# meca_2014_VaccumSystemExtension.net
KiCad netlist of a schematic drawn in EAGLE
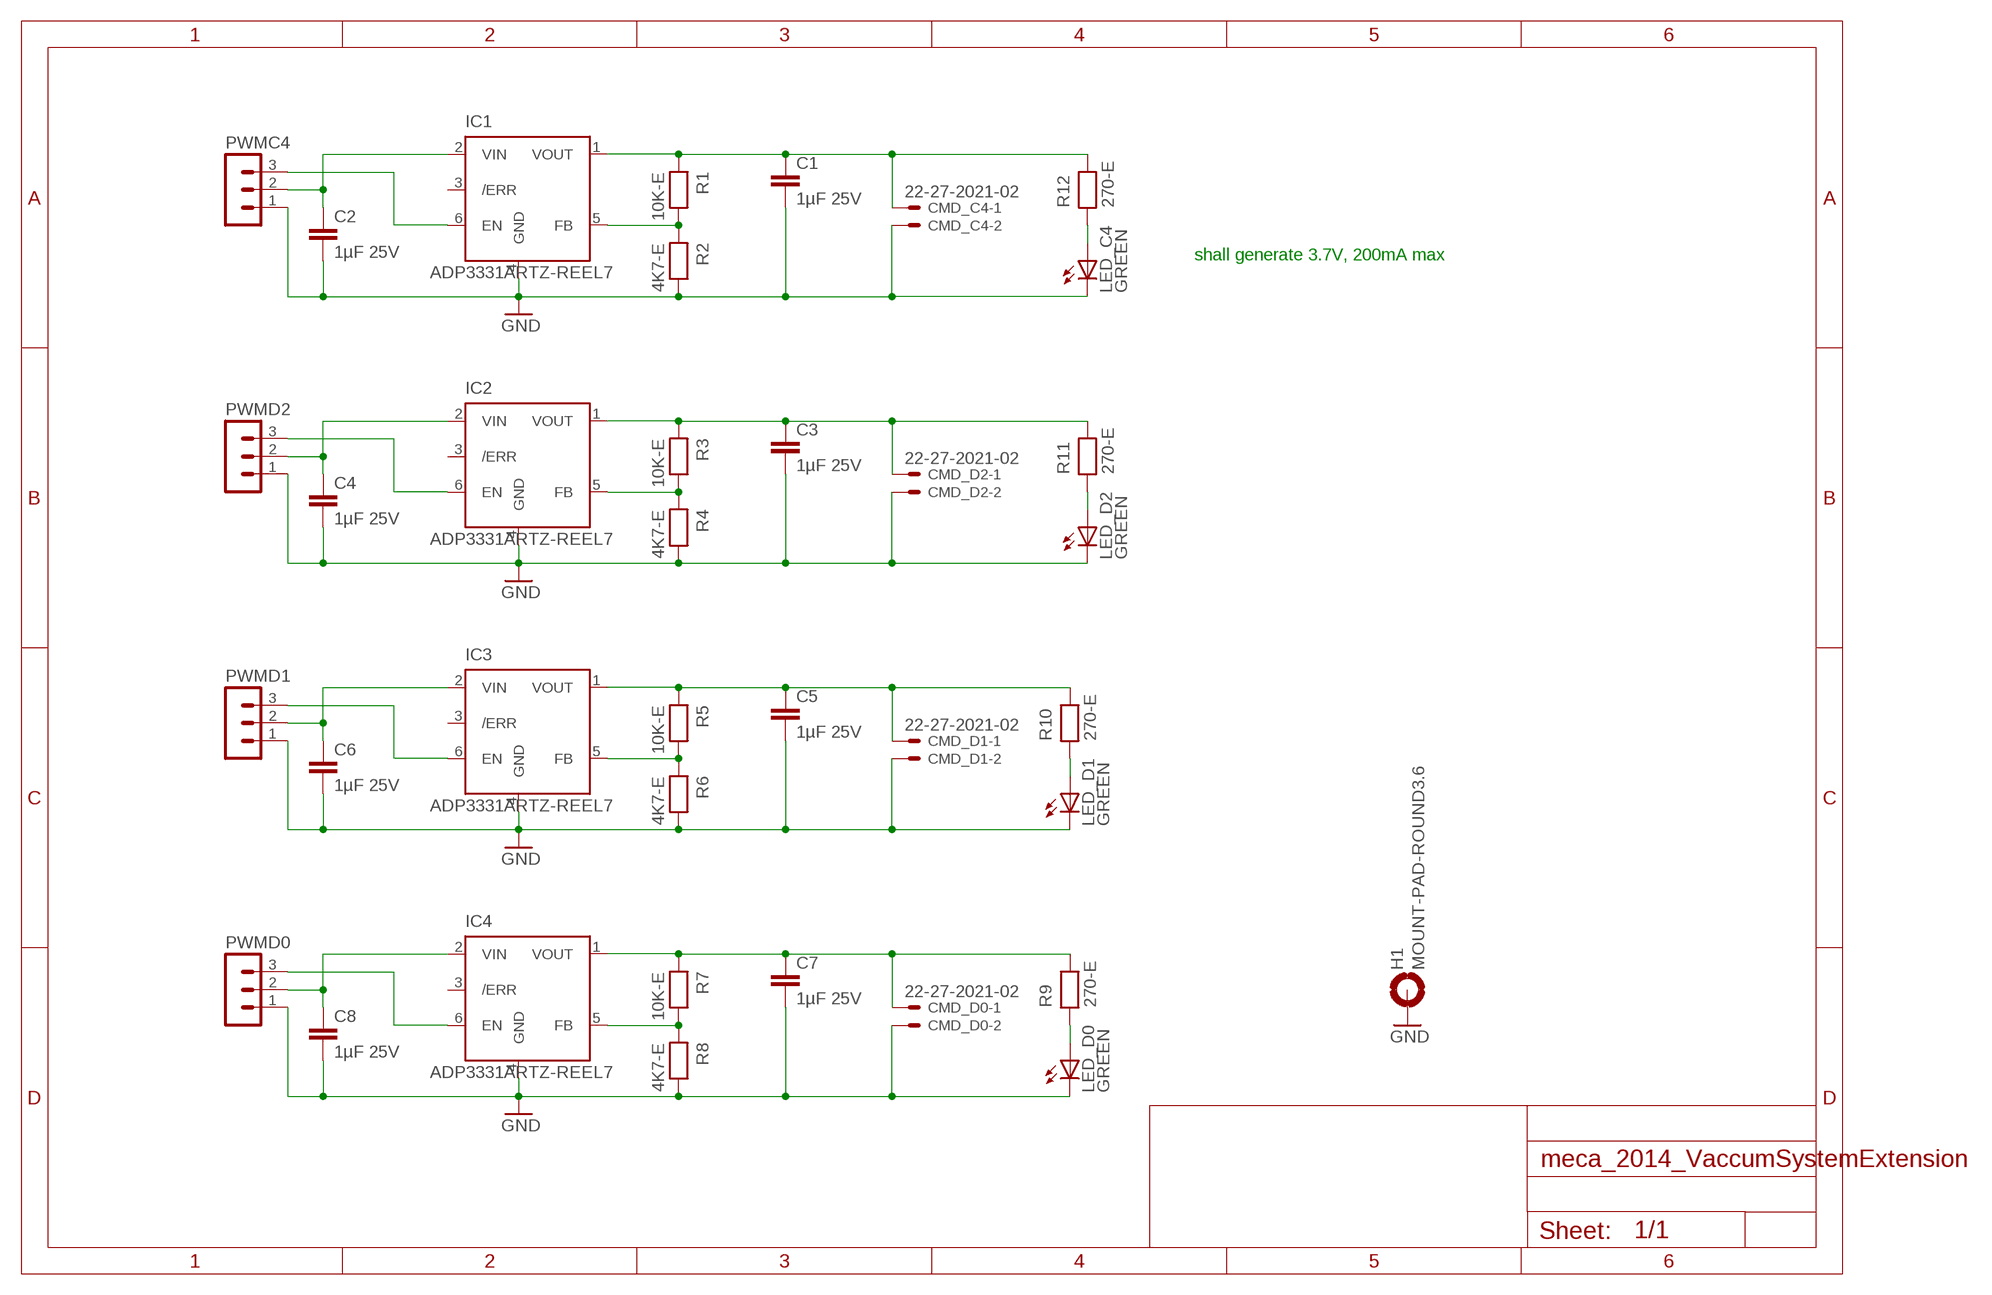
[diagram p0: schematic, sheet 1]

(export (version "E")
  (design (tool "Eeschema 10.0.6"))
  (components
    (comp (ref "C1")
      (value "1µF 25V")
      (footprint "eagle-import:C1206")
      (libsource (lib "eagle-import") (part "1UFD_25V"))
    )
    (comp (ref "C2")
      (value "1µF 25V")
      (footprint "eagle-import:C1206")
      (libsource (lib "eagle-import") (part "1UFD_25V"))
    )
    (comp (ref "C3")
      (value "1µF 25V")
      (footprint "eagle-import:C1206")
      (libsource (lib "eagle-import") (part "1UFD_25V"))
    )
    (comp (ref "C4")
      (value "1µF 25V")
      (footprint "eagle-import:C1206")
      (libsource (lib "eagle-import") (part "1UFD_25V"))
    )
    (comp (ref "C5")
      (value "1µF 25V")
      (footprint "eagle-import:C1206")
      (libsource (lib "eagle-import") (part "1UFD_25V"))
    )
    (comp (ref "C6")
      (value "1µF 25V")
      (footprint "eagle-import:C1206")
      (libsource (lib "eagle-import") (part "1UFD_25V"))
    )
    (comp (ref "C7")
      (value "1µF 25V")
      (footprint "eagle-import:C1206")
      (libsource (lib "eagle-import") (part "1UFD_25V"))
    )
    (comp (ref "C8")
      (value "1µF 25V")
      (footprint "eagle-import:C1206")
      (libsource (lib "eagle-import") (part "1UFD_25V"))
    )
    (comp (ref "CMD_C4")
      (value "22-27-2021-02")
      (footprint "eagle-import:6410-02")
      (libsource (lib "eagle-import") (part "22-?-0227-2021"))
    )
    (comp (ref "CMD_D0")
      (value "22-27-2021-02")
      (footprint "eagle-import:6410-02")
      (libsource (lib "eagle-import") (part "22-?-0227-2021"))
    )
    (comp (ref "CMD_D1")
      (value "22-27-2021-02")
      (footprint "eagle-import:6410-02")
      (libsource (lib "eagle-import") (part "22-?-0227-2021"))
    )
    (comp (ref "CMD_D2")
      (value "22-27-2021-02")
      (footprint "eagle-import:6410-02")
      (libsource (lib "eagle-import") (part "22-?-0227-2021"))
    )
    (comp (ref "H1")
      (value "MOUNT-PAD-ROUND3.6")
      (footprint "eagle-import:3,6-PAD")
      (libsource (lib "eagle-import") (part "MOUNT-PAD-ROUND3.6"))
    )
    (comp (ref "IC1")
      (value "ADP3331ARTZ-REEL7")
      (footprint "eagle-import:SOT23-6")
      (libsource (lib "eagle-import") (part "ADP3331ARTZ-REEL7"))
    )
    (comp (ref "IC2")
      (value "ADP3331ARTZ-REEL7")
      (footprint "eagle-import:SOT23-6")
      (libsource (lib "eagle-import") (part "ADP3331ARTZ-REEL7"))
    )
    (comp (ref "IC3")
      (value "ADP3331ARTZ-REEL7")
      (footprint "eagle-import:SOT23-6")
      (libsource (lib "eagle-import") (part "ADP3331ARTZ-REEL7"))
    )
    (comp (ref "IC4")
      (value "ADP3331ARTZ-REEL7")
      (footprint "eagle-import:SOT23-6")
      (libsource (lib "eagle-import") (part "ADP3331ARTZ-REEL7"))
    )
    (comp (ref "LED_C4")
      (value "GREEN")
      (footprint "eagle-import:CHIP-LED0805")
      (libsource (lib "eagle-import") (part "LED_G"))
    )
    (comp (ref "LED_D0")
      (value "GREEN")
      (footprint "eagle-import:CHIP-LED0805")
      (libsource (lib "eagle-import") (part "LED_G"))
    )
    (comp (ref "LED_D1")
      (value "GREEN")
      (footprint "eagle-import:CHIP-LED0805")
      (libsource (lib "eagle-import") (part "LED_G"))
    )
    (comp (ref "LED_D2")
      (value "GREEN")
      (footprint "eagle-import:CHIP-LED0805")
      (libsource (lib "eagle-import") (part "LED_G"))
    )
    (comp (ref "PWMC4")
      (value "MA03-1")
      (footprint "eagle-import:MA03-1")
      (libsource (lib "eagle-import") (part "MA03-1"))
    )
    (comp (ref "PWMD0")
      (value "MA03-1")
      (footprint "eagle-import:MA03-1")
      (libsource (lib "eagle-import") (part "MA03-1"))
    )
    (comp (ref "PWMD1")
      (value "MA03-1")
      (footprint "eagle-import:MA03-1")
      (libsource (lib "eagle-import") (part "MA03-1"))
    )
    (comp (ref "PWMD2")
      (value "MA03-1")
      (footprint "eagle-import:MA03-1")
      (libsource (lib "eagle-import") (part "MA03-1"))
    )
    (comp (ref "R1")
      (value "10K-E")
      (footprint "eagle-import:R0805")
      (libsource (lib "eagle-import") (part "10K-E"))
    )
    (comp (ref "R2")
      (value "4K7-E")
      (footprint "eagle-import:R0805")
      (libsource (lib "eagle-import") (part "4K7-E"))
    )
    (comp (ref "R3")
      (value "10K-E")
      (footprint "eagle-import:R0805")
      (libsource (lib "eagle-import") (part "10K-E"))
    )
    (comp (ref "R4")
      (value "4K7-E")
      (footprint "eagle-import:R0805")
      (libsource (lib "eagle-import") (part "4K7-E"))
    )
    (comp (ref "R5")
      (value "10K-E")
      (footprint "eagle-import:R0805")
      (libsource (lib "eagle-import") (part "10K-E"))
    )
    (comp (ref "R6")
      (value "4K7-E")
      (footprint "eagle-import:R0805")
      (libsource (lib "eagle-import") (part "4K7-E"))
    )
    (comp (ref "R7")
      (value "10K-E")
      (footprint "eagle-import:R0805")
      (libsource (lib "eagle-import") (part "10K-E"))
    )
    (comp (ref "R8")
      (value "4K7-E")
      (footprint "eagle-import:R0805")
      (libsource (lib "eagle-import") (part "4K7-E"))
    )
    (comp (ref "R9")
      (value "270-E")
      (footprint "eagle-import:R0805")
      (libsource (lib "eagle-import") (part "270-E"))
    )
    (comp (ref "R10")
      (value "270-E")
      (footprint "eagle-import:R0805")
      (libsource (lib "eagle-import") (part "270-E"))
    )
    (comp (ref "R11")
      (value "270-E")
      (footprint "eagle-import:R0805")
      (libsource (lib "eagle-import") (part "270-E"))
    )
    (comp (ref "R12")
      (value "270-E")
      (footprint "eagle-import:R0805")
      (libsource (lib "eagle-import") (part "270-E"))
    )
  )
  (nets
    (net (code "1") (name "GND") (class "Default")
      (node (ref "C1") (pin "2") (pinfunction "2_2") (pintype "passive"))
      (node (ref "C2") (pin "2") (pinfunction "2_2") (pintype "passive"))
      (node (ref "C3") (pin "2") (pinfunction "2_2") (pintype "passive"))
      (node (ref "C4") (pin "2") (pinfunction "2_2") (pintype "passive"))
      (node (ref "C5") (pin "2") (pinfunction "2_2") (pintype "passive"))
      (node (ref "C6") (pin "2") (pinfunction "2_2") (pintype "passive"))
      (node (ref "C7") (pin "2") (pinfunction "2_2") (pintype "passive"))
      (node (ref "C8") (pin "2") (pinfunction "2_2") (pintype "passive"))
      (node (ref "CMD_C4") (pin "2") (pinfunction "S_2") (pintype "passive"))
      (node (ref "CMD_D0") (pin "2") (pinfunction "S_2") (pintype "passive"))
      (node (ref "CMD_D1") (pin "2") (pinfunction "S_2") (pintype "passive"))
      (node (ref "CMD_D2") (pin "2") (pinfunction "S_2") (pintype "passive"))
      (node (ref "H1") (pin "B3,6") (pinfunction "MOUNT_B3,6") (pintype "passive"))
      (node (ref "IC1") (pin "4") (pinfunction "GND_4") (pintype "bidirectional"))
      (node (ref "IC2") (pin "4") (pinfunction "GND_4") (pintype "bidirectional"))
      (node (ref "IC3") (pin "4") (pinfunction "GND_4") (pintype "bidirectional"))
      (node (ref "IC4") (pin "4") (pinfunction "GND_4") (pintype "bidirectional"))
      (node (ref "LED_C4") (pin "C") (pinfunction "C_C") (pintype "passive"))
      (node (ref "LED_D0") (pin "C") (pinfunction "C_C") (pintype "passive"))
      (node (ref "LED_D1") (pin "C") (pinfunction "C_C") (pintype "passive"))
      (node (ref "LED_D2") (pin "C") (pinfunction "C_C") (pintype "passive"))
      (node (ref "PWMC4") (pin "1") (pinfunction "1_1") (pintype "passive"))
      (node (ref "PWMD0") (pin "1") (pinfunction "1_1") (pintype "passive"))
      (node (ref "PWMD1") (pin "1") (pinfunction "1_1") (pintype "passive"))
      (node (ref "PWMD2") (pin "1") (pinfunction "1_1") (pintype "passive"))
      (node (ref "R2") (pin "2") (pinfunction "2_2") (pintype "bidirectional"))
      (node (ref "R4") (pin "2") (pinfunction "2_2") (pintype "bidirectional"))
      (node (ref "R6") (pin "2") (pinfunction "2_2") (pintype "bidirectional"))
      (node (ref "R8") (pin "2") (pinfunction "2_2") (pintype "bidirectional"))
    )
    (net (code "2") (name "Net-(CMD_C4A-S)") (class "Default")
      (node (ref "C1") (pin "1") (pinfunction "1_1") (pintype "passive"))
      (node (ref "CMD_C4") (pin "1") (pinfunction "S_1") (pintype "passive"))
      (node (ref "IC1") (pin "1") (pinfunction "VOUT_1") (pintype "bidirectional"))
      (node (ref "R1") (pin "1") (pinfunction "1_1") (pintype "bidirectional"))
      (node (ref "R12") (pin "2") (pinfunction "2_2") (pintype "bidirectional"))
    )
    (net (code "3") (name "Net-(CMD_D0A-S)") (class "Default")
      (node (ref "C7") (pin "1") (pinfunction "1_1") (pintype "passive"))
      (node (ref "CMD_D0") (pin "1") (pinfunction "S_1") (pintype "passive"))
      (node (ref "IC4") (pin "1") (pinfunction "VOUT_1") (pintype "bidirectional"))
      (node (ref "R7") (pin "1") (pinfunction "1_1") (pintype "bidirectional"))
      (node (ref "R9") (pin "2") (pinfunction "2_2") (pintype "bidirectional"))
    )
    (net (code "4") (name "Net-(CMD_D1A-S)") (class "Default")
      (node (ref "C5") (pin "1") (pinfunction "1_1") (pintype "passive"))
      (node (ref "CMD_D1") (pin "1") (pinfunction "S_1") (pintype "passive"))
      (node (ref "IC3") (pin "1") (pinfunction "VOUT_1") (pintype "bidirectional"))
      (node (ref "R10") (pin "2") (pinfunction "2_2") (pintype "bidirectional"))
      (node (ref "R5") (pin "1") (pinfunction "1_1") (pintype "bidirectional"))
    )
    (net (code "5") (name "Net-(CMD_D2A-S)") (class "Default")
      (node (ref "C3") (pin "1") (pinfunction "1_1") (pintype "passive"))
      (node (ref "CMD_D2") (pin "1") (pinfunction "S_1") (pintype "passive"))
      (node (ref "IC2") (pin "1") (pinfunction "VOUT_1") (pintype "bidirectional"))
      (node (ref "R11") (pin "2") (pinfunction "2_2") (pintype "bidirectional"))
      (node (ref "R3") (pin "1") (pinfunction "1_1") (pintype "bidirectional"))
    )
    (net (code "6") (name "Net-(IC1-EN)") (class "Default")
      (node (ref "IC1") (pin "6") (pinfunction "EN_6") (pintype "bidirectional"))
      (node (ref "PWMC4") (pin "3") (pinfunction "3_3") (pintype "passive"))
    )
    (net (code "7") (name "Net-(IC1-FB)") (class "Default")
      (node (ref "IC1") (pin "5") (pinfunction "FB_5") (pintype "bidirectional"))
      (node (ref "R1") (pin "2") (pinfunction "2_2") (pintype "bidirectional"))
      (node (ref "R2") (pin "1") (pinfunction "1_1") (pintype "bidirectional"))
    )
    (net (code "8") (name "Net-(IC1-VIN)") (class "Default")
      (node (ref "C2") (pin "1") (pinfunction "1_1") (pintype "passive"))
      (node (ref "IC1") (pin "2") (pinfunction "VIN_2") (pintype "bidirectional"))
      (node (ref "PWMC4") (pin "2") (pinfunction "2_2") (pintype "passive"))
    )
    (net (code "9") (name "Net-(IC2-EN)") (class "Default")
      (node (ref "IC2") (pin "6") (pinfunction "EN_6") (pintype "bidirectional"))
      (node (ref "PWMD2") (pin "3") (pinfunction "3_3") (pintype "passive"))
    )
    (net (code "10") (name "Net-(IC2-FB)") (class "Default")
      (node (ref "IC2") (pin "5") (pinfunction "FB_5") (pintype "bidirectional"))
      (node (ref "R3") (pin "2") (pinfunction "2_2") (pintype "bidirectional"))
      (node (ref "R4") (pin "1") (pinfunction "1_1") (pintype "bidirectional"))
    )
    (net (code "11") (name "Net-(IC2-VIN)") (class "Default")
      (node (ref "C4") (pin "1") (pinfunction "1_1") (pintype "passive"))
      (node (ref "IC2") (pin "2") (pinfunction "VIN_2") (pintype "bidirectional"))
      (node (ref "PWMD2") (pin "2") (pinfunction "2_2") (pintype "passive"))
    )
    (net (code "12") (name "Net-(IC3-EN)") (class "Default")
      (node (ref "IC3") (pin "6") (pinfunction "EN_6") (pintype "bidirectional"))
      (node (ref "PWMD1") (pin "3") (pinfunction "3_3") (pintype "passive"))
    )
    (net (code "13") (name "Net-(IC3-FB)") (class "Default")
      (node (ref "IC3") (pin "5") (pinfunction "FB_5") (pintype "bidirectional"))
      (node (ref "R5") (pin "2") (pinfunction "2_2") (pintype "bidirectional"))
      (node (ref "R6") (pin "1") (pinfunction "1_1") (pintype "bidirectional"))
    )
    (net (code "14") (name "Net-(IC3-VIN)") (class "Default")
      (node (ref "C6") (pin "1") (pinfunction "1_1") (pintype "passive"))
      (node (ref "IC3") (pin "2") (pinfunction "VIN_2") (pintype "bidirectional"))
      (node (ref "PWMD1") (pin "2") (pinfunction "2_2") (pintype "passive"))
    )
    (net (code "15") (name "Net-(IC4-EN)") (class "Default")
      (node (ref "IC4") (pin "6") (pinfunction "EN_6") (pintype "bidirectional"))
      (node (ref "PWMD0") (pin "3") (pinfunction "3_3") (pintype "passive"))
    )
    (net (code "16") (name "Net-(IC4-FB)") (class "Default")
      (node (ref "IC4") (pin "5") (pinfunction "FB_5") (pintype "bidirectional"))
      (node (ref "R7") (pin "2") (pinfunction "2_2") (pintype "bidirectional"))
      (node (ref "R8") (pin "1") (pinfunction "1_1") (pintype "bidirectional"))
    )
    (net (code "17") (name "Net-(IC4-VIN)") (class "Default")
      (node (ref "C8") (pin "1") (pinfunction "1_1") (pintype "passive"))
      (node (ref "IC4") (pin "2") (pinfunction "VIN_2") (pintype "bidirectional"))
      (node (ref "PWMD0") (pin "2") (pinfunction "2_2") (pintype "passive"))
    )
    (net (code "18") (name "Net-(LED_C4-PadA)") (class "Default")
      (node (ref "LED_C4") (pin "A") (pinfunction "A_A") (pintype "passive"))
      (node (ref "R12") (pin "1") (pinfunction "1_1") (pintype "bidirectional"))
    )
    (net (code "19") (name "Net-(LED_D0-PadA)") (class "Default")
      (node (ref "LED_D0") (pin "A") (pinfunction "A_A") (pintype "passive"))
      (node (ref "R9") (pin "1") (pinfunction "1_1") (pintype "bidirectional"))
    )
    (net (code "20") (name "Net-(LED_D1-PadA)") (class "Default")
      (node (ref "LED_D1") (pin "A") (pinfunction "A_A") (pintype "passive"))
      (node (ref "R10") (pin "1") (pinfunction "1_1") (pintype "bidirectional"))
    )
    (net (code "21") (name "Net-(LED_D2-PadA)") (class "Default")
      (node (ref "LED_D2") (pin "A") (pinfunction "A_A") (pintype "passive"))
      (node (ref "R11") (pin "1") (pinfunction "1_1") (pintype "bidirectional"))
    )
    (net (code "22") (name "unconnected-(IC1-{slash}ERR-Pad3)") (class "Default")
      (node (ref "IC1") (pin "3") (pinfunction "/ERR_3") (pintype "bidirectional"))
    )
    (net (code "23") (name "unconnected-(IC2-{slash}ERR-Pad3)") (class "Default")
      (node (ref "IC2") (pin "3") (pinfunction "/ERR_3") (pintype "bidirectional"))
    )
    (net (code "24") (name "unconnected-(IC3-{slash}ERR-Pad3)") (class "Default")
      (node (ref "IC3") (pin "3") (pinfunction "/ERR_3") (pintype "bidirectional"))
    )
    (net (code "25") (name "unconnected-(IC4-{slash}ERR-Pad3)") (class "Default")
      (node (ref "IC4") (pin "3") (pinfunction "/ERR_3") (pintype "bidirectional"))
    )
  )
)
